# protoBoard.net
KiCad netlist of a schematic drawn in EAGLE
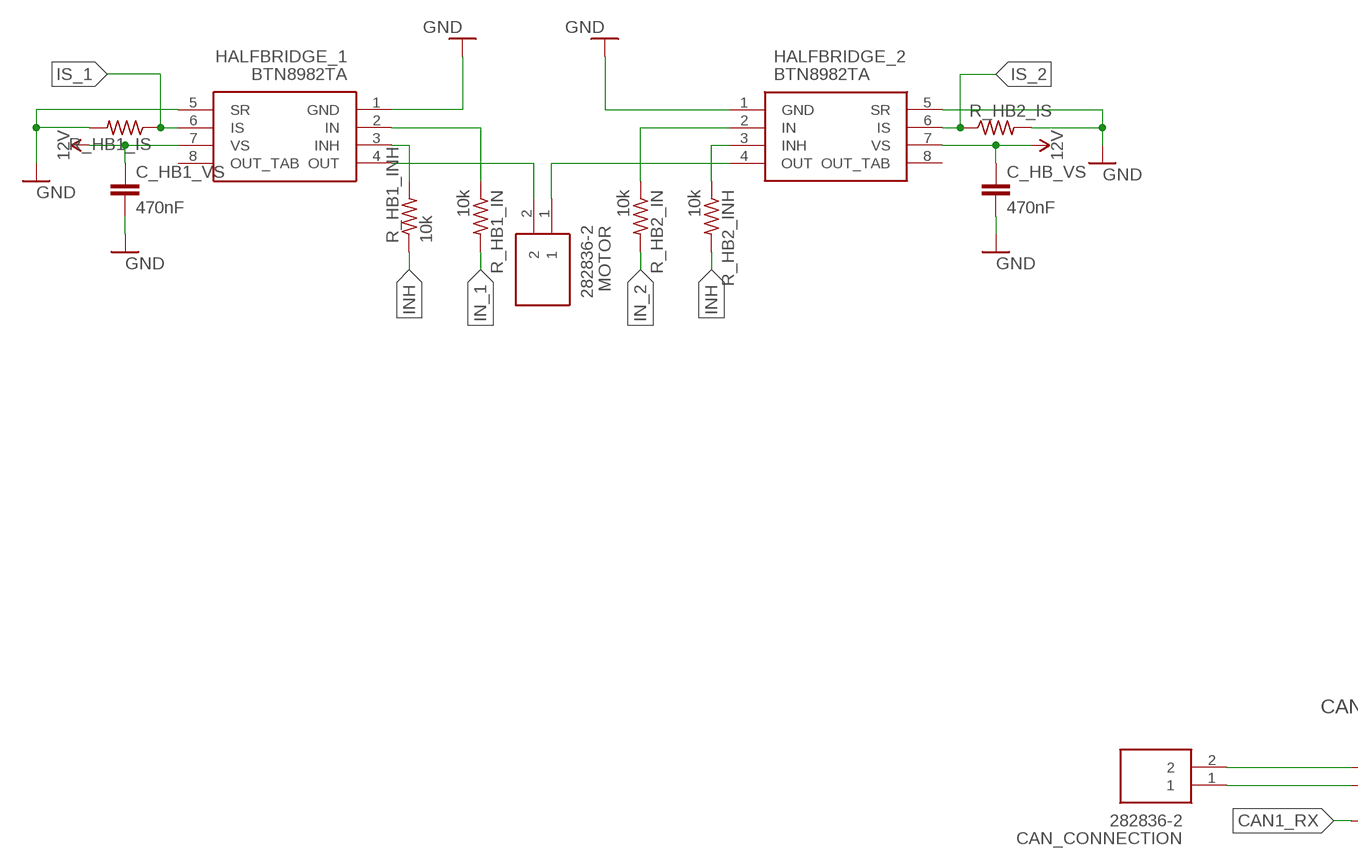
[diagram p0: schematic, sheet 1, part 1 of 2]
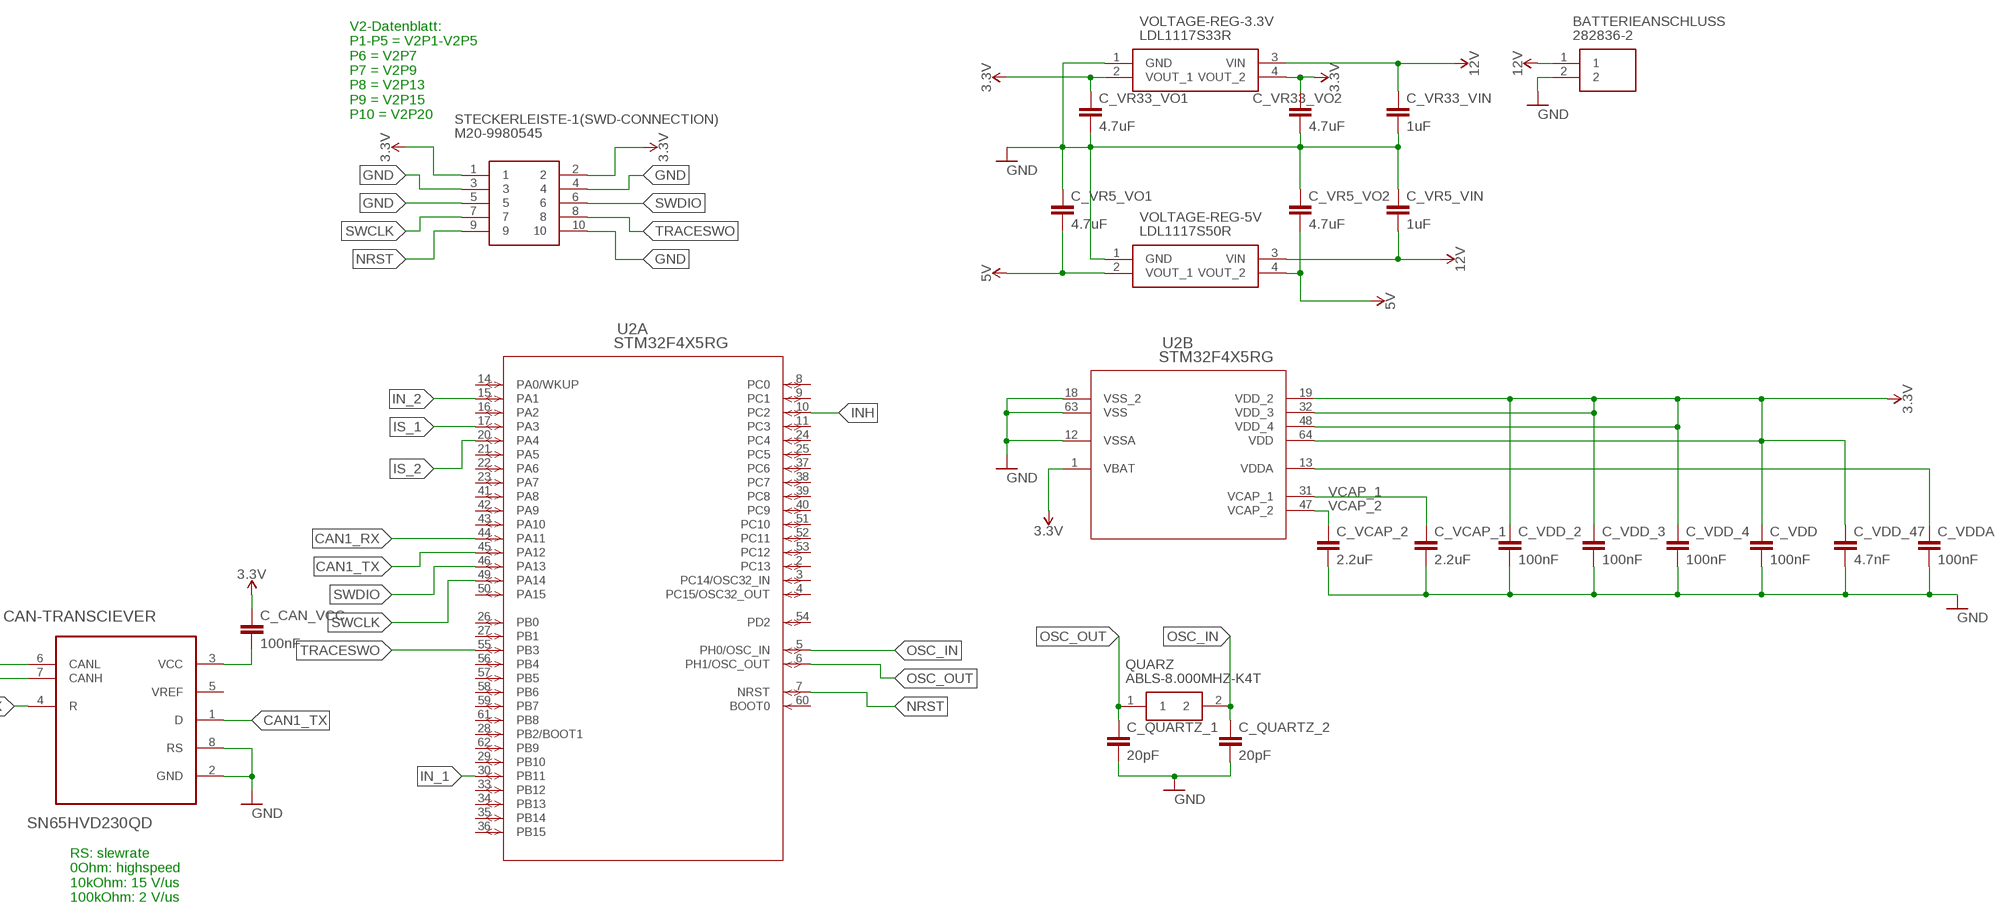
[diagram p1: schematic, sheet 1, part 2 of 2]

(export (version "E")
  (design (tool "Eeschema 10.0.6"))
  (components
    (comp (ref "BATTERIEANSCHLUSS")
      (value "282836-2")
      (footprint "eagle-import:SHDR2W100P0X500_1X2_1000X820X1")
      (fields (field (name "MOUSER_PART_NUMBER") "571-2828362"))
      (libsource (lib "eagle-import") (part "282836-2"))
    )
    (comp (ref "CAN-TRANSCIEVER")
      (value "SN65HVD230QD")
      (footprint "eagle-import:SOIC127P600X175-8N")
      (fields (field (name "MF") "TEXAS INSTRUMENTS") (field (name "MPN") "SN65HVD230QD.."))
      (libsource (lib "eagle-import") (part "SN65HVD230QD"))
    )
    (comp (ref "CAN_CONNECTION")
      (value "282836-2")
      (footprint "eagle-import:SHDR2W100P0X500_1X2_1000X820X1")
      (fields (field (name "MOUSER_PART_NUMBER") "571-2828362"))
      (libsource (lib "eagle-import") (part "282836-2"))
    )
    (comp (ref "C_CAN_VCC")
      (value "100nF")
      (footprint "eagle-import:C2.5-6")
      (libsource (lib "eagle-import") (part "C2.5/6"))
    )
    (comp (ref "C_HB1_VS")
      (value "470nF")
      (footprint "eagle-import:C2.5-6")
      (libsource (lib "eagle-import") (part "C2.5/6"))
    )
    (comp (ref "C_HB_VS")
      (value "470nF")
      (footprint "eagle-import:C2.5-6")
      (libsource (lib "eagle-import") (part "C2.5/6"))
    )
    (comp (ref "C_QUARTZ_1")
      (value "20pF")
      (footprint "eagle-import:C2.5-6")
      (libsource (lib "eagle-import") (part "C2.5/6"))
    )
    (comp (ref "C_QUARTZ_2")
      (value "20pF")
      (footprint "eagle-import:C2.5-6")
      (libsource (lib "eagle-import") (part "C2.5/6"))
    )
    (comp (ref "C_VCAP_1")
      (value "2.2uF")
      (footprint "eagle-import:C2.5-6")
      (libsource (lib "eagle-import") (part "C2.5/6"))
    )
    (comp (ref "C_VCAP_2")
      (value "2.2uF")
      (footprint "eagle-import:C2.5-6")
      (libsource (lib "eagle-import") (part "C2.5/6"))
    )
    (comp (ref "C_VDD")
      (value "100nF")
      (footprint "eagle-import:C2.5-6")
      (libsource (lib "eagle-import") (part "C2.5/6"))
    )
    (comp (ref "C_VDDA")
      (value "100nF")
      (footprint "eagle-import:C2.5-6")
      (libsource (lib "eagle-import") (part "C2.5/6"))
    )
    (comp (ref "C_VDD_2")
      (value "100nF")
      (footprint "eagle-import:C2.5-6")
      (libsource (lib "eagle-import") (part "C2.5/6"))
    )
    (comp (ref "C_VDD_3")
      (value "100nF")
      (footprint "eagle-import:C2.5-6")
      (libsource (lib "eagle-import") (part "C2.5/6"))
    )
    (comp (ref "C_VDD_4")
      (value "100nF")
      (footprint "eagle-import:C2.5-6")
      (libsource (lib "eagle-import") (part "C2.5/6"))
    )
    (comp (ref "C_VDD_47")
      (value "4.7nF")
      (footprint "eagle-import:C2.5-6")
      (libsource (lib "eagle-import") (part "C2.5/6"))
    )
    (comp (ref "C_VR5_VIN")
      (value "1uF")
      (footprint "eagle-import:C2.5-6")
      (libsource (lib "eagle-import") (part "C2.5/6"))
    )
    (comp (ref "C_VR5_VO1")
      (value "4.7uF")
      (footprint "eagle-import:C2.5-6")
      (libsource (lib "eagle-import") (part "C2.5/6"))
    )
    (comp (ref "C_VR5_VO2")
      (value "4.7uF")
      (footprint "eagle-import:C2.5-6")
      (libsource (lib "eagle-import") (part "C2.5/6"))
    )
    (comp (ref "C_VR33_VIN")
      (value "1uF")
      (footprint "eagle-import:C2.5-6")
      (libsource (lib "eagle-import") (part "C2.5/6"))
    )
    (comp (ref "C_VR33_VO1")
      (value "4.7uF")
      (footprint "eagle-import:C2.5-6")
      (libsource (lib "eagle-import") (part "C2.5/6"))
    )
    (comp (ref "C_VR33_VO2")
      (value "4.7uF")
      (footprint "eagle-import:C2.5-6")
      (libsource (lib "eagle-import") (part "C2.5/6"))
    )
    (comp (ref "HALFBRIDGE_1")
      (value "BTN8982TA")
      (footprint "eagle-import:TO127P1500X440-8N")
      (fields (field (name "MOUSER_PART_NUMBER") "726-BTN8982TA"))
      (libsource (lib "eagle-import") (part "BTN8982TA"))
    )
    (comp (ref "HALFBRIDGE_2")
      (value "BTN8982TA")
      (footprint "eagle-import:TO127P1500X440-8N")
      (fields (field (name "MOUSER_PART_NUMBER") "726-BTN8982TA"))
      (libsource (lib "eagle-import") (part "BTN8982TA"))
    )
    (comp (ref "MOTOR")
      (value "282836-2")
      (footprint "eagle-import:SHDR2W100P0X500_1X2_1000X820X1")
      (fields (field (name "MOUSER_PART_NUMBER") "571-2828362"))
      (libsource (lib "eagle-import") (part "282836-2"))
    )
    (comp (ref "QUARZ")
      (value "ABLS-8.000MHZ-K4T")
      (footprint "eagle-import:ABLS-12.000MHZ-B2")
      (fields (field (name "MOUSER_PART_NUMBER") "815-ABLS-8.0MK4-T") (field (name "MF") "ABRACON"))
      (libsource (lib "eagle-import") (part "ABLS-8.000MHZ-K4T"))
    )
    (comp (ref "R_HB1_IN")
      (value "10k")
      (footprint "eagle-import:0204_7")
      (libsource (lib "eagle-import") (part "R-US_0204/7"))
    )
    (comp (ref "R_HB1_INH")
      (value "10k")
      (footprint "eagle-import:0204_7")
      (libsource (lib "eagle-import") (part "R-US_0204/7"))
    )
    (comp (ref "R_HB1_IS")
      (value "R-US_0204/7")
      (footprint "eagle-import:0204_7")
      (libsource (lib "eagle-import") (part "R-US_0204/7"))
    )
    (comp (ref "R_HB2_IN")
      (value "10k")
      (footprint "eagle-import:0204_7")
      (libsource (lib "eagle-import") (part "R-US_0204/7"))
    )
    (comp (ref "R_HB2_INH")
      (value "10k")
      (footprint "eagle-import:0204_7")
      (libsource (lib "eagle-import") (part "R-US_0204/7"))
    )
    (comp (ref "R_HB2_IS")
      (value "R-US_0204/7")
      (footprint "eagle-import:0204_7")
      (libsource (lib "eagle-import") (part "R-US_0204/7"))
    )
    (comp (ref "STECKERLEISTE-1(SWD-CONNECTION)")
      (value "M20-9980545")
      (footprint "eagle-import:HDRV10W80P254_2X5_1270X508X864")
      (fields (field (name "MOUSER_PART_NUMBER") "855-M20-9980545") (field (name "MF") "HARWIN"))
      (libsource (lib "eagle-import") (part "M20-9980545"))
    )
    (comp (ref "U2")
      (value "STM32F4X5RG")
      (footprint "eagle-import:LQFP64-10X10MM")
      (fields (field (name "OC_FARNELL") "unknown"))
      (libsource (lib "eagle-import") (part "STM32F4X5RG"))
    )
    (comp (ref "VOLTAGE-REG-3.3V")
      (value "LDL1117S33R")
      (footprint "eagle-import:SOT230P700X180-4N")
      (fields (field (name "MOUSER_PART_NUMBER") "511-LDL1117S33R") (field (name "MF") "STMICROELECTRONICS"))
      (libsource (lib "eagle-import") (part "LDL1117S33R"))
    )
    (comp (ref "VOLTAGE-REG-5V")
      (value "LDL1117S50R")
      (footprint "eagle-import:SOT230P700X180-4N")
      (fields (field (name "MOUSER_PART_NUMBER") "511-LDL1117S50R") (field (name "MF") "STMICROELECTRONICS"))
      (libsource (lib "eagle-import") (part "LDL1117S50R"))
    )
  )
  (nets
    (net (code "1") (name "/VCAP_1") (class "Default")
      (node (ref "C_VCAP_1") (pin "1") (pinfunction "1_1") (pintype "passive"))
      (node (ref "U2") (pin "31") (pinfunction "VCAP_1_31") (pintype "power_in"))
    )
    (net (code "2") (name "/VCAP_2") (class "Default")
      (node (ref "C_VCAP_2") (pin "1") (pinfunction "1_1") (pintype "passive"))
      (node (ref "U2") (pin "47") (pinfunction "VCAP_2_47") (pintype "power_in"))
    )
    (net (code "3") (name "3.3V") (class "Default")
      (node (ref "C_CAN_VCC") (pin "1") (pinfunction "1_1") (pintype "passive"))
      (node (ref "C_VDD") (pin "1") (pinfunction "1_1") (pintype "passive"))
      (node (ref "C_VDD_2") (pin "1") (pinfunction "1_1") (pintype "passive"))
      (node (ref "C_VDD_3") (pin "1") (pinfunction "1_1") (pintype "passive"))
      (node (ref "C_VDD_4") (pin "1") (pinfunction "1_1") (pintype "passive"))
      (node (ref "C_VDD_47") (pin "1") (pinfunction "1_1") (pintype "passive"))
      (node (ref "C_VR33_VO1") (pin "1") (pinfunction "1_1") (pintype "passive"))
      (node (ref "C_VR33_VO2") (pin "1") (pinfunction "1_1") (pintype "passive"))
      (node (ref "C_VR5_VO1") (pin "2") (pinfunction "2_2") (pintype "passive"))
      (node (ref "C_VR5_VO2") (pin "2") (pinfunction "2_2") (pintype "passive"))
      (node (ref "STECKERLEISTE-1(SWD-CONNECTION)") (pin "1") (pinfunction "1_1") (pintype "bidirectional"))
      (node (ref "STECKERLEISTE-1(SWD-CONNECTION)") (pin "2") (pinfunction "2_2") (pintype "bidirectional"))
      (node (ref "U2") (pin "1") (pinfunction "VBAT_1") (pintype "power_in"))
      (node (ref "U2") (pin "19") (pinfunction "VDD_2_19") (pintype "power_in"))
      (node (ref "U2") (pin "32") (pinfunction "VDD_3_32") (pintype "power_in"))
      (node (ref "U2") (pin "48") (pinfunction "VDD_4_48") (pintype "power_in"))
      (node (ref "U2") (pin "64") (pinfunction "VDD_64") (pintype "power_in"))
      (node (ref "VOLTAGE-REG-3.3V") (pin "2") (pinfunction "VOUT_1_2") (pintype "output"))
      (node (ref "VOLTAGE-REG-3.3V") (pin "4") (pinfunction "VOUT_2_4") (pintype "output"))
      (node (ref "VOLTAGE-REG-5V") (pin "2") (pinfunction "VOUT_1_2") (pintype "bidirectional"))
      (node (ref "VOLTAGE-REG-5V") (pin "4") (pinfunction "VOUT_2_4") (pintype "bidirectional"))
    )
    (net (code "4") (name "12V") (class "Default")
      (node (ref "BATTERIEANSCHLUSS") (pin "1") (pinfunction "1_1") (pintype "bidirectional"))
      (node (ref "C_HB1_VS") (pin "1") (pinfunction "1_1") (pintype "passive"))
      (node (ref "C_HB_VS") (pin "1") (pinfunction "1_1") (pintype "passive"))
      (node (ref "C_VR33_VIN") (pin "1") (pinfunction "1_1") (pintype "passive"))
      (node (ref "C_VR5_VIN") (pin "2") (pinfunction "2_2") (pintype "passive"))
      (node (ref "HALFBRIDGE_1") (pin "7") (pinfunction "VS_7") (pintype "bidirectional"))
      (node (ref "HALFBRIDGE_2") (pin "7") (pinfunction "VS_7") (pintype "bidirectional"))
      (node (ref "VOLTAGE-REG-3.3V") (pin "3") (pinfunction "VIN_3") (pintype "input"))
      (node (ref "VOLTAGE-REG-5V") (pin "3") (pinfunction "VIN_3") (pintype "bidirectional"))
    )
    (net (code "5") (name "CAN1_RX") (class "Default")
      (node (ref "CAN-TRANSCIEVER") (pin "4") (pinfunction "R_4") (pintype "output"))
      (node (ref "U2") (pin "44") (pinfunction "PA11_44") (pintype "bidirectional"))
    )
    (net (code "6") (name "CAN1_TX") (class "Default")
      (node (ref "CAN-TRANSCIEVER") (pin "1") (pinfunction "D_1") (pintype "input"))
      (node (ref "U2") (pin "45") (pinfunction "PA12_45") (pintype "bidirectional"))
    )
    (net (code "7") (name "GND") (class "Default")
      (node (ref "BATTERIEANSCHLUSS") (pin "2") (pinfunction "2_2") (pintype "bidirectional"))
      (node (ref "CAN-TRANSCIEVER") (pin "2") (pinfunction "GND_2") (pintype "passive"))
      (node (ref "CAN-TRANSCIEVER") (pin "8") (pinfunction "RS_8") (pintype "input"))
      (node (ref "C_HB1_VS") (pin "2") (pinfunction "2_2") (pintype "passive"))
      (node (ref "C_HB_VS") (pin "2") (pinfunction "2_2") (pintype "passive"))
      (node (ref "C_QUARTZ_1") (pin "2") (pinfunction "2_2") (pintype "passive"))
      (node (ref "C_QUARTZ_2") (pin "2") (pinfunction "2_2") (pintype "passive"))
      (node (ref "C_VCAP_1") (pin "2") (pinfunction "2_2") (pintype "passive"))
      (node (ref "C_VCAP_2") (pin "2") (pinfunction "2_2") (pintype "passive"))
      (node (ref "C_VDD") (pin "2") (pinfunction "2_2") (pintype "passive"))
      (node (ref "C_VDDA") (pin "2") (pinfunction "2_2") (pintype "passive"))
      (node (ref "C_VDD_2") (pin "2") (pinfunction "2_2") (pintype "passive"))
      (node (ref "C_VDD_3") (pin "2") (pinfunction "2_2") (pintype "passive"))
      (node (ref "C_VDD_4") (pin "2") (pinfunction "2_2") (pintype "passive"))
      (node (ref "C_VDD_47") (pin "2") (pinfunction "2_2") (pintype "passive"))
      (node (ref "C_VR33_VIN") (pin "2") (pinfunction "2_2") (pintype "passive"))
      (node (ref "C_VR33_VO1") (pin "2") (pinfunction "2_2") (pintype "passive"))
      (node (ref "C_VR33_VO2") (pin "2") (pinfunction "2_2") (pintype "passive"))
      (node (ref "C_VR5_VIN") (pin "1") (pinfunction "1_1") (pintype "passive"))
      (node (ref "C_VR5_VO1") (pin "1") (pinfunction "1_1") (pintype "passive"))
      (node (ref "C_VR5_VO2") (pin "1") (pinfunction "1_1") (pintype "passive"))
      (node (ref "HALFBRIDGE_1") (pin "1") (pinfunction "GND_1") (pintype "power_in"))
      (node (ref "HALFBRIDGE_1") (pin "5") (pinfunction "SR_5") (pintype "bidirectional"))
      (node (ref "HALFBRIDGE_2") (pin "1") (pinfunction "GND_1") (pintype "power_in"))
      (node (ref "HALFBRIDGE_2") (pin "5") (pinfunction "SR_5") (pintype "bidirectional"))
      (node (ref "R_HB1_IS") (pin "2") (pinfunction "2_2") (pintype "passive"))
      (node (ref "R_HB2_IS") (pin "2") (pinfunction "2_2") (pintype "passive"))
      (node (ref "STECKERLEISTE-1(SWD-CONNECTION)") (pin "10") (pinfunction "10_10") (pintype "bidirectional"))
      (node (ref "STECKERLEISTE-1(SWD-CONNECTION)") (pin "3") (pinfunction "3_3") (pintype "bidirectional"))
      (node (ref "STECKERLEISTE-1(SWD-CONNECTION)") (pin "4") (pinfunction "4_4") (pintype "bidirectional"))
      (node (ref "STECKERLEISTE-1(SWD-CONNECTION)") (pin "5") (pinfunction "5_5") (pintype "bidirectional"))
      (node (ref "U2") (pin "12") (pinfunction "VSSA_12") (pintype "power_in"))
      (node (ref "U2") (pin "18") (pinfunction "VSS_2_18") (pintype "power_in"))
      (node (ref "U2") (pin "63") (pinfunction "VSS_63") (pintype "power_in"))
      (node (ref "VOLTAGE-REG-3.3V") (pin "1") (pinfunction "GND_1") (pintype "power_in"))
      (node (ref "VOLTAGE-REG-5V") (pin "1") (pinfunction "GND_1") (pintype "bidirectional"))
    )
    (net (code "8") (name "INH") (class "Default")
      (node (ref "R_HB1_INH") (pin "1") (pinfunction "1_1") (pintype "passive"))
      (node (ref "R_HB2_INH") (pin "2") (pinfunction "2_2") (pintype "passive"))
      (node (ref "U2") (pin "10") (pinfunction "PC2_10") (pintype "bidirectional"))
    )
    (net (code "9") (name "IN_1") (class "Default")
      (node (ref "R_HB1_IN") (pin "2") (pinfunction "2_2") (pintype "passive"))
      (node (ref "U2") (pin "30") (pinfunction "PB11_30") (pintype "bidirectional"))
    )
    (net (code "10") (name "IN_2") (class "Default")
      (node (ref "R_HB2_IN") (pin "2") (pinfunction "2_2") (pintype "passive"))
      (node (ref "U2") (pin "15") (pinfunction "PA1_15") (pintype "bidirectional"))
    )
    (net (code "11") (name "IS_1") (class "Default")
      (node (ref "HALFBRIDGE_1") (pin "6") (pinfunction "IS_6") (pintype "bidirectional"))
      (node (ref "R_HB1_IS") (pin "1") (pinfunction "1_1") (pintype "passive"))
      (node (ref "U2") (pin "17") (pinfunction "PA3_17") (pintype "bidirectional"))
    )
    (net (code "12") (name "IS_2") (class "Default")
      (node (ref "HALFBRIDGE_2") (pin "6") (pinfunction "IS_6") (pintype "bidirectional"))
      (node (ref "R_HB2_IS") (pin "1") (pinfunction "1_1") (pintype "passive"))
      (node (ref "U2") (pin "20") (pinfunction "PA4_20") (pintype "bidirectional"))
    )
    (net (code "13") (name "NRST") (class "Default")
      (node (ref "STECKERLEISTE-1(SWD-CONNECTION)") (pin "9") (pinfunction "9_9") (pintype "bidirectional"))
      (node (ref "U2") (pin "7") (pinfunction "NRST_7") (pintype "bidirectional"))
    )
    (net (code "14") (name "Net-(CAN-TRANSCIEVER-CANH)") (class "Default")
      (node (ref "CAN-TRANSCIEVER") (pin "7") (pinfunction "CANH_7") (pintype "output"))
      (node (ref "CAN_CONNECTION") (pin "1") (pinfunction "1_1") (pintype "bidirectional"))
    )
    (net (code "15") (name "Net-(CAN-TRANSCIEVER-CANL)") (class "Default")
      (node (ref "CAN-TRANSCIEVER") (pin "6") (pinfunction "CANL_6") (pintype "output"))
      (node (ref "CAN_CONNECTION") (pin "2") (pinfunction "2_2") (pintype "bidirectional"))
    )
    (net (code "16") (name "Net-(CAN-TRANSCIEVER-VCC)") (class "Default")
      (node (ref "CAN-TRANSCIEVER") (pin "3") (pinfunction "VCC_3") (pintype "power_in"))
      (node (ref "C_CAN_VCC") (pin "2") (pinfunction "2_2") (pintype "passive"))
    )
    (net (code "17") (name "Net-(HALFBRIDGE_1-IN)") (class "Default")
      (node (ref "HALFBRIDGE_1") (pin "2") (pinfunction "IN_2") (pintype "input"))
      (node (ref "R_HB1_IN") (pin "1") (pinfunction "1_1") (pintype "passive"))
    )
    (net (code "18") (name "Net-(HALFBRIDGE_1-INH)") (class "Default")
      (node (ref "HALFBRIDGE_1") (pin "3") (pinfunction "INH_3") (pintype "input"))
      (node (ref "R_HB1_INH") (pin "2") (pinfunction "2_2") (pintype "passive"))
    )
    (net (code "19") (name "Net-(HALFBRIDGE_1-OUT)") (class "Default")
      (node (ref "HALFBRIDGE_1") (pin "4") (pinfunction "OUT_4") (pintype "output"))
      (node (ref "MOTOR") (pin "2") (pinfunction "2_2") (pintype "bidirectional"))
    )
    (net (code "20") (name "Net-(HALFBRIDGE_2-IN)") (class "Default")
      (node (ref "HALFBRIDGE_2") (pin "2") (pinfunction "IN_2") (pintype "input"))
      (node (ref "R_HB2_IN") (pin "1") (pinfunction "1_1") (pintype "passive"))
    )
    (net (code "21") (name "Net-(HALFBRIDGE_2-INH)") (class "Default")
      (node (ref "HALFBRIDGE_2") (pin "3") (pinfunction "INH_3") (pintype "input"))
      (node (ref "R_HB2_INH") (pin "1") (pinfunction "1_1") (pintype "passive"))
    )
    (net (code "22") (name "Net-(HALFBRIDGE_2-OUT)") (class "Default")
      (node (ref "HALFBRIDGE_2") (pin "4") (pinfunction "OUT_4") (pintype "output"))
      (node (ref "MOTOR") (pin "1") (pinfunction "1_1") (pintype "bidirectional"))
    )
    (net (code "23") (name "Net-(U2B-VDDA)") (class "Default")
      (node (ref "C_VDDA") (pin "1") (pinfunction "1_1") (pintype "passive"))
      (node (ref "U2") (pin "13") (pinfunction "VDDA_13") (pintype "power_in"))
    )
    (net (code "24") (name "OSC_IN") (class "Default")
      (node (ref "C_QUARTZ_2") (pin "1") (pinfunction "1_1") (pintype "passive"))
      (node (ref "QUARZ") (pin "2") (pinfunction "2_2") (pintype "bidirectional"))
      (node (ref "U2") (pin "5") (pinfunction "PH0/OSC_IN_5") (pintype "bidirectional"))
    )
    (net (code "25") (name "OSC_OUT") (class "Default")
      (node (ref "C_QUARTZ_1") (pin "1") (pinfunction "1_1") (pintype "passive"))
      (node (ref "QUARZ") (pin "1") (pinfunction "1_1") (pintype "bidirectional"))
      (node (ref "U2") (pin "6") (pinfunction "PH1/OSC_OUT_6") (pintype "bidirectional"))
    )
    (net (code "26") (name "SWCLK") (class "Default")
      (node (ref "STECKERLEISTE-1(SWD-CONNECTION)") (pin "7") (pinfunction "7_7") (pintype "bidirectional"))
      (node (ref "U2") (pin "49") (pinfunction "PA14_49") (pintype "bidirectional"))
    )
    (net (code "27") (name "SWDIO") (class "Default")
      (node (ref "STECKERLEISTE-1(SWD-CONNECTION)") (pin "6") (pinfunction "6_6") (pintype "bidirectional"))
      (node (ref "U2") (pin "46") (pinfunction "PA13_46") (pintype "bidirectional"))
    )
    (net (code "28") (name "TRACESWO") (class "Default")
      (node (ref "STECKERLEISTE-1(SWD-CONNECTION)") (pin "8") (pinfunction "8_8") (pintype "bidirectional"))
      (node (ref "U2") (pin "55") (pinfunction "PB3_55") (pintype "bidirectional"))
    )
    (net (code "29") (name "unconnected-(CAN-TRANSCIEVER-VREF-Pad5)") (class "Default")
      (node (ref "CAN-TRANSCIEVER") (pin "5") (pinfunction "VREF_5") (pintype "input"))
    )
    (net (code "30") (name "unconnected-(HALFBRIDGE_1-OUT_TAB-Pad8)") (class "Default")
      (node (ref "HALFBRIDGE_1") (pin "8") (pinfunction "OUT_TAB_8") (pintype "output"))
    )
    (net (code "31") (name "unconnected-(HALFBRIDGE_2-OUT_TAB-Pad8)") (class "Default")
      (node (ref "HALFBRIDGE_2") (pin "8") (pinfunction "OUT_TAB_8") (pintype "output"))
    )
    (net (code "32") (name "unconnected-(U2A-BOOT0-Pad60)") (class "Default")
      (node (ref "U2") (pin "60") (pinfunction "BOOT0_60") (pintype "input"))
    )
    (net (code "33") (name "unconnected-(U2A-PA0{slash}WKUP-Pad14)") (class "Default")
      (node (ref "U2") (pin "14") (pinfunction "PA0/WKUP_14") (pintype "bidirectional"))
    )
    (net (code "34") (name "unconnected-(U2A-PA2-Pad16)") (class "Default")
      (node (ref "U2") (pin "16") (pinfunction "PA2_16") (pintype "bidirectional"))
    )
    (net (code "35") (name "unconnected-(U2A-PA5-Pad21)") (class "Default")
      (node (ref "U2") (pin "21") (pinfunction "PA5_21") (pintype "bidirectional"))
    )
    (net (code "36") (name "unconnected-(U2A-PA6-Pad22)") (class "Default")
      (node (ref "U2") (pin "22") (pinfunction "PA6_22") (pintype "bidirectional"))
    )
    (net (code "37") (name "unconnected-(U2A-PA7-Pad23)") (class "Default")
      (node (ref "U2") (pin "23") (pinfunction "PA7_23") (pintype "bidirectional"))
    )
    (net (code "38") (name "unconnected-(U2A-PA8-Pad41)") (class "Default")
      (node (ref "U2") (pin "41") (pinfunction "PA8_41") (pintype "bidirectional"))
    )
    (net (code "39") (name "unconnected-(U2A-PA9-Pad42)") (class "Default")
      (node (ref "U2") (pin "42") (pinfunction "PA9_42") (pintype "bidirectional"))
    )
    (net (code "40") (name "unconnected-(U2A-PA10-Pad43)") (class "Default")
      (node (ref "U2") (pin "43") (pinfunction "PA10_43") (pintype "bidirectional"))
    )
    (net (code "41") (name "unconnected-(U2A-PA15-Pad50)") (class "Default")
      (node (ref "U2") (pin "50") (pinfunction "PA15_50") (pintype "bidirectional"))
    )
    (net (code "42") (name "unconnected-(U2A-PB0-Pad26)") (class "Default")
      (node (ref "U2") (pin "26") (pinfunction "PB0_26") (pintype "bidirectional"))
    )
    (net (code "43") (name "unconnected-(U2A-PB1-Pad27)") (class "Default")
      (node (ref "U2") (pin "27") (pinfunction "PB1_27") (pintype "bidirectional"))
    )
    (net (code "44") (name "unconnected-(U2A-PB2{slash}BOOT1-Pad28)") (class "Default")
      (node (ref "U2") (pin "28") (pinfunction "PB2/BOOT1_28") (pintype "bidirectional"))
    )
    (net (code "45") (name "unconnected-(U2A-PB4-Pad56)") (class "Default")
      (node (ref "U2") (pin "56") (pinfunction "PB4_56") (pintype "bidirectional"))
    )
    (net (code "46") (name "unconnected-(U2A-PB5-Pad57)") (class "Default")
      (node (ref "U2") (pin "57") (pinfunction "PB5_57") (pintype "bidirectional"))
    )
    (net (code "47") (name "unconnected-(U2A-PB6-Pad58)") (class "Default")
      (node (ref "U2") (pin "58") (pinfunction "PB6_58") (pintype "bidirectional"))
    )
    (net (code "48") (name "unconnected-(U2A-PB7-Pad59)") (class "Default")
      (node (ref "U2") (pin "59") (pinfunction "PB7_59") (pintype "bidirectional"))
    )
    (net (code "49") (name "unconnected-(U2A-PB8-Pad61)") (class "Default")
      (node (ref "U2") (pin "61") (pinfunction "PB8_61") (pintype "bidirectional"))
    )
    (net (code "50") (name "unconnected-(U2A-PB9-Pad62)") (class "Default")
      (node (ref "U2") (pin "62") (pinfunction "PB9_62") (pintype "bidirectional"))
    )
    (net (code "51") (name "unconnected-(U2A-PB10-Pad29)") (class "Default")
      (node (ref "U2") (pin "29") (pinfunction "PB10_29") (pintype "bidirectional"))
    )
    (net (code "52") (name "unconnected-(U2A-PB12-Pad33)") (class "Default")
      (node (ref "U2") (pin "33") (pinfunction "PB12_33") (pintype "bidirectional"))
    )
    (net (code "53") (name "unconnected-(U2A-PB13-Pad34)") (class "Default")
      (node (ref "U2") (pin "34") (pinfunction "PB13_34") (pintype "bidirectional"))
    )
    (net (code "54") (name "unconnected-(U2A-PB14-Pad35)") (class "Default")
      (node (ref "U2") (pin "35") (pinfunction "PB14_35") (pintype "bidirectional"))
    )
    (net (code "55") (name "unconnected-(U2A-PB15-Pad36)") (class "Default")
      (node (ref "U2") (pin "36") (pinfunction "PB15_36") (pintype "bidirectional"))
    )
    (net (code "56") (name "unconnected-(U2A-PC0-Pad8)") (class "Default")
      (node (ref "U2") (pin "8") (pinfunction "PC0_8") (pintype "bidirectional"))
    )
    (net (code "57") (name "unconnected-(U2A-PC1-Pad9)") (class "Default")
      (node (ref "U2") (pin "9") (pinfunction "PC1_9") (pintype "bidirectional"))
    )
    (net (code "58") (name "unconnected-(U2A-PC3-Pad11)") (class "Default")
      (node (ref "U2") (pin "11") (pinfunction "PC3_11") (pintype "bidirectional"))
    )
    (net (code "59") (name "unconnected-(U2A-PC4-Pad24)") (class "Default")
      (node (ref "U2") (pin "24") (pinfunction "PC4_24") (pintype "bidirectional"))
    )
    (net (code "60") (name "unconnected-(U2A-PC5-Pad25)") (class "Default")
      (node (ref "U2") (pin "25") (pinfunction "PC5_25") (pintype "bidirectional"))
    )
    (net (code "61") (name "unconnected-(U2A-PC6-Pad37)") (class "Default")
      (node (ref "U2") (pin "37") (pinfunction "PC6_37") (pintype "bidirectional"))
    )
    (net (code "62") (name "unconnected-(U2A-PC7-Pad38)") (class "Default")
      (node (ref "U2") (pin "38") (pinfunction "PC7_38") (pintype "bidirectional"))
    )
    (net (code "63") (name "unconnected-(U2A-PC8-Pad39)") (class "Default")
      (node (ref "U2") (pin "39") (pinfunction "PC8_39") (pintype "bidirectional"))
    )
    (net (code "64") (name "unconnected-(U2A-PC9-Pad40)") (class "Default")
      (node (ref "U2") (pin "40") (pinfunction "PC9_40") (pintype "bidirectional"))
    )
    (net (code "65") (name "unconnected-(U2A-PC10-Pad51)") (class "Default")
      (node (ref "U2") (pin "51") (pinfunction "PC10_51") (pintype "bidirectional"))
    )
    (net (code "66") (name "unconnected-(U2A-PC11-Pad52)") (class "Default")
      (node (ref "U2") (pin "52") (pinfunction "PC11_52") (pintype "bidirectional"))
    )
    (net (code "67") (name "unconnected-(U2A-PC12-Pad53)") (class "Default")
      (node (ref "U2") (pin "53") (pinfunction "PC12_53") (pintype "bidirectional"))
    )
    (net (code "68") (name "unconnected-(U2A-PC13-Pad2)") (class "Default")
      (node (ref "U2") (pin "2") (pinfunction "PC13_2") (pintype "bidirectional"))
    )
    (net (code "69") (name "unconnected-(U2A-PC14{slash}OSC32_IN-Pad3)") (class "Default")
      (node (ref "U2") (pin "3") (pinfunction "PC14/OSC32_IN_3") (pintype "bidirectional"))
    )
    (net (code "70") (name "unconnected-(U2A-PC15{slash}OSC32_OUT-Pad4)") (class "Default")
      (node (ref "U2") (pin "4") (pinfunction "PC15/OSC32_OUT_4") (pintype "bidirectional"))
    )
    (net (code "71") (name "unconnected-(U2A-PD2-Pad54)") (class "Default")
      (node (ref "U2") (pin "54") (pinfunction "PD2_54") (pintype "bidirectional"))
    )
  )
)
